# Isolated_Op_Amp.net
KiCad netlist of a schematic drawn in Altium Designer
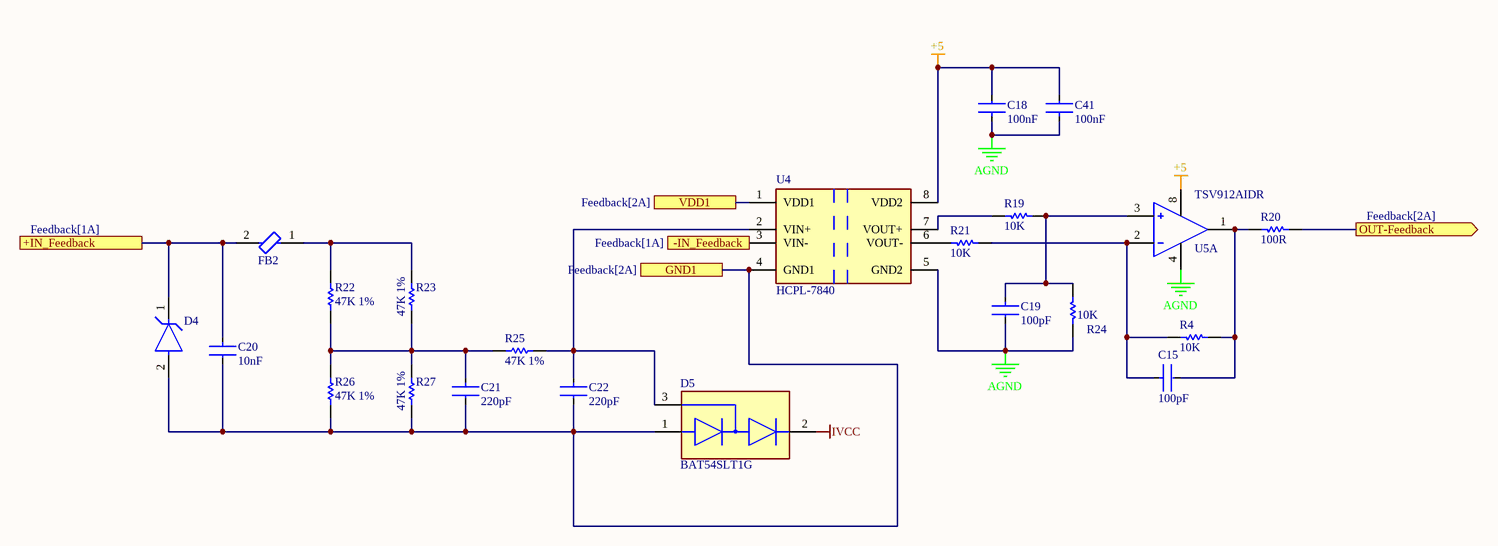
[diagram p0: Isolated Op Amp.SchDoc]

(export (version "E")
  (design (tool "Eeschema 10.0.6"))
  (components
    (comp (ref "C15")
      (value "100pF")
      (footprint "Hosein_PCB_Lib_SMD:CAP-0805")
      (description "Chip Multilayer Ceramic Capacitors for General Purpose, 0603")
      (fields (field (name "VOLTAGE") "6.3V") (field (name "TOLERANCE") "20%"))
      (libsource (lib "Hosein_PCB_Lib") (part "CAP-Ceramic"))
    )
    (comp (ref "C18")
      (value "100nF")
      (footprint "Hosein_PCB_Lib_SMD:CAP-0805")
      (description "Chip Multilayer Ceramic Capacitors for General Purpose, 0603")
      (fields (field (name "VOLTAGE") "6.3V") (field (name "TOLERANCE") "20%"))
      (libsource (lib "Hosein_PCB_Lib") (part "CAP-Ceramic"))
    )
    (comp (ref "C19")
      (value "100pF")
      (footprint "Hosein_PCB_Lib_SMD:CAP-0805")
      (description "Chip Multilayer Ceramic Capacitors for General Purpose, 0603")
      (fields (field (name "VOLTAGE") "6.3V") (field (name "TOLERANCE") "20%"))
      (libsource (lib "Hosein_PCB_Lib") (part "CAP-Ceramic"))
    )
    (comp (ref "C20")
      (value "10nF")
      (footprint "Hosein_PCB_Lib_SMD:CAP-0805")
      (description "Chip Multilayer Ceramic Capacitors for General Purpose, 0603")
      (fields (field (name "VOLTAGE") "6.3V") (field (name "TOLERANCE") "20%"))
      (libsource (lib "Hosein_PCB_Lib") (part "CAP-Ceramic"))
    )
    (comp (ref "C21")
      (value "220pF")
      (footprint "Hosein_PCB_Lib_SMD:CAP-0805")
      (description "Chip Multilayer Ceramic Capacitors for General Purpose, 0603")
      (fields (field (name "VOLTAGE") "6.3V") (field (name "TOLERANCE") "20%"))
      (libsource (lib "Hosein_PCB_Lib") (part "CAP-Ceramic"))
    )
    (comp (ref "C22")
      (value "220pF")
      (footprint "Hosein_PCB_Lib_SMD:CAP-0805")
      (description "Chip Multilayer Ceramic Capacitors for General Purpose, 0603")
      (fields (field (name "VOLTAGE") "6.3V") (field (name "TOLERANCE") "20%"))
      (libsource (lib "Hosein_PCB_Lib") (part "CAP-Ceramic"))
    )
    (comp (ref "C41")
      (value "100nF")
      (footprint "Hosein_PCB_Lib_SMD:CAP-0805")
      (description "Chip Multilayer Ceramic Capacitors for General Purpose, 0603")
      (fields (field (name "VOLTAGE") "6.3V") (field (name "TOLERANCE") "20%"))
      (libsource (lib "Hosein_PCB_Lib") (part "CAP-Ceramic"))
    )
    (comp (ref "D4")
      (value "SMBJ12")
      (footprint "FP-SMB-MFG")
      (description "TVS DIODE SMB")
      (fields
        (field (name "MANUFACTURER") "STMicroelectronics")
        (field (name "MANUFACTURER PART NUMBER") "SMBJ5.0A-TR")
      )
      (libsource (lib "Altium Content Vault") (part "7ddec9f632b8482e96f7745d0fbdf39"))
    )
    (comp (ref "D5")
      (value "BAT54SLT1G")
      (footprint "FP-318-08-IPC_B")
      (description "DIODE ARRAY SCHOTTKY 30V SOT23-3")
      (libsource (lib "Altium Content Vault") (part "cd4ed45a2b9de5095685adb7d6d9b5b"))
    )
    (comp (ref "FB2")
      (value "Ferrite Bead")
      (footprint "FP-BLM31-0_2-t1_1-MFG")
      (description "1206")
      (fields (field (name "TOLERANCE") "25%"))
      (libsource (lib "Altium Content Vault") (part "5f30dd21d616792df468990f7003faa"))
    )
    (comp (ref "R4")
      (value "10K")
      (footprint "Hosein_PCB_Lib_SMD:RES-0805")
      (description "Chip Resistor")
      (fields (field (name "MANUFACTURER") "Vishay Semiconductor"))
      (libsource (lib "Hosein_PCB_Lib") (part "RES_SMD"))
    )
    (comp (ref "R19")
      (value "10K")
      (footprint "Hosein_PCB_Lib_SMD:RES-0805")
      (description "Chip Resistor")
      (fields (field (name "MANUFACTURER") "Vishay Semiconductor"))
      (libsource (lib "Hosein_PCB_Lib") (part "RES_SMD"))
    )
    (comp (ref "R20")
      (value "100R")
      (footprint "Hosein_PCB_Lib_SMD:RES-0805")
      (description "Chip Resistor")
      (fields (field (name "MANUFACTURER") "Vishay Semiconductor"))
      (libsource (lib "Hosein_PCB_Lib") (part "RES_SMD"))
    )
    (comp (ref "R21")
      (value "10K")
      (footprint "Hosein_PCB_Lib_SMD:RES-0805")
      (description "Chip Resistor")
      (fields (field (name "MANUFACTURER") "Vishay Semiconductor"))
      (libsource (lib "Hosein_PCB_Lib") (part "RES_SMD"))
    )
    (comp (ref "R22")
      (value "47K 1%")
      (footprint "Hosein_PCB_Lib_SMD:RES-0805")
      (description "Resistor")
      (fields
        (field (name "TOLERANCE") "5%")
        (field (name "POWER") "1/8 W")
        (field (name "DESIGNER") "Eng. Saeid Jorablo")
        (field (name "PUBLISHER") "SJ Unlimited")
      )
      (libsource (lib "Passive Components") (part "RES"))
    )
    (comp (ref "R23")
      (value "47K 1%")
      (footprint "Hosein_PCB_Lib_SMD:RES-0805")
      (description "Resistor")
      (fields
        (field (name "TOLERANCE") "5%")
        (field (name "POWER") "1/8 W")
        (field (name "DESIGNER") "Eng. Saeid Jorablo")
        (field (name "PUBLISHER") "SJ Unlimited")
      )
      (libsource (lib "Passive Components") (part "RES"))
    )
    (comp (ref "R24")
      (value "10K")
      (footprint "Hosein_PCB_Lib_SMD:RES-0805")
      (description "Chip Resistor")
      (fields (field (name "MANUFACTURER") "Vishay Semiconductor"))
      (libsource (lib "Hosein_PCB_Lib") (part "RES_SMD"))
    )
    (comp (ref "R25")
      (value "47K 1%")
      (footprint "Hosein_PCB_Lib_SMD:RES-0805")
      (description "Resistor")
      (fields
        (field (name "TOLERANCE") "5%")
        (field (name "POWER") "1/8 W")
        (field (name "DESIGNER") "Eng. Saeid Jorablo")
        (field (name "PUBLISHER") "SJ Unlimited")
      )
      (libsource (lib "Passive Components") (part "RES"))
    )
    (comp (ref "R26")
      (value "47K 1%")
      (footprint "Hosein_PCB_Lib_SMD:RES-0805")
      (description "Resistor")
      (fields
        (field (name "TOLERANCE") "5%")
        (field (name "POWER") "1/8 W")
        (field (name "DESIGNER") "Eng. Saeid Jorablo")
        (field (name "PUBLISHER") "SJ Unlimited")
      )
      (libsource (lib "Passive Components") (part "RES"))
    )
    (comp (ref "R27")
      (value "47K 1%")
      (footprint "Hosein_PCB_Lib_SMD:RES-0805")
      (description "Resistor")
      (fields
        (field (name "TOLERANCE") "5%")
        (field (name "POWER") "1/8 W")
        (field (name "DESIGNER") "Eng. Saeid Jorablo")
        (field (name "PUBLISHER") "SJ Unlimited")
      )
      (libsource (lib "Passive Components") (part "RES"))
    )
    (comp (ref "U4")
      (value "HCPL-7840")
      (footprint "FP-HCPL-7800-000E-MFG")
      (description "IC OPAMP ISOLATION 1 CIRC 8DIP")
      (fields (field (name "VOLTAGE") "5V"))
      (libsource (lib "Altium Content Vault") (part "2f7dad3764c767f6029bf863b3cb099"))
    )
    (comp (ref "U5")
      (value "TSV912AIDR")
      (footprint "FP-D0008A-MFG")
      (description "IC OPAMP GP 2 CIRCUIT 8SOIC")
      (libsource (lib "Altium Content Vault") (part "9685343c43c352196e7b040df9e4583"))
    )
  )
  (nets
    (net (code "1") (name "+5") (class "Default")
      (node (ref "C18") (pin "2") (pinfunction "2_2") (pintype "passive"))
      (node (ref "C41") (pin "2") (pinfunction "2_2") (pintype "passive"))
      (node (ref "U4") (pin "8") (pinfunction "VDD2_8") (pintype "power_in"))
      (node (ref "U5") (pin "8") (pinfunction "V+_8") (pintype "power_in"))
    )
    (net (code "2") (name "/+IN_Feedback") (class "Default")
      (node (ref "C20") (pin "1") (pinfunction "1_1") (pintype "passive"))
      (node (ref "D4") (pin "1") (pinfunction "K_1") (pintype "passive"))
      (node (ref "FB2") (pin "2") (pinfunction "2_2") (pintype "passive"))
    )
    (net (code "3") (name "/-IN_Feedback") (class "Default")
      (node (ref "U4") (pin "3") (pinfunction "VIN-_3") (pintype "passive"))
    )
    (net (code "4") (name "/GND1") (class "Default")
      (node (ref "C20") (pin "2") (pinfunction "2_2") (pintype "passive"))
      (node (ref "C21") (pin "2") (pinfunction "2_2") (pintype "passive"))
      (node (ref "C22") (pin "2") (pinfunction "2_2") (pintype "passive"))
      (node (ref "D4") (pin "2") (pinfunction "A_2") (pintype "passive"))
      (node (ref "D5") (pin "1") (pinfunction "A_1") (pintype "passive"))
      (node (ref "R26") (pin "2") (pinfunction "2_2") (pintype "passive"))
      (node (ref "R27") (pin "1") (pinfunction "1_1") (pintype "passive"))
      (node (ref "U4") (pin "4") (pinfunction "GND1_4") (pintype "power_in"))
    )
    (net (code "5") (name "/OUT-Feedback") (class "Default")
      (node (ref "R20") (pin "1") (pinfunction "1_1") (pintype "passive"))
    )
    (net (code "6") (name "/VDD1") (class "Default")
      (node (ref "U4") (pin "1") (pinfunction "VDD1_1") (pintype "power_in"))
    )
    (net (code "7") (name "AGND") (class "Default")
      (node (ref "C18") (pin "1") (pinfunction "1_1") (pintype "passive"))
      (node (ref "C19") (pin "2") (pinfunction "2_2") (pintype "passive"))
      (node (ref "C41") (pin "1") (pinfunction "1_1") (pintype "passive"))
      (node (ref "R24") (pin "1") (pinfunction "1_1") (pintype "passive"))
      (node (ref "U4") (pin "5") (pinfunction "GND2_5") (pintype "power_in"))
      (node (ref "U5") (pin "4") (pinfunction "V-_4") (pintype "power_in"))
    )
    (net (code "8") (name "IVCC") (class "Default")
      (node (ref "D5") (pin "2") (pinfunction "C_2") (pintype "passive"))
    )
    (net (code "9") (name "Net-(C21-Pad1)") (class "Default")
      (node (ref "C21") (pin "1") (pinfunction "1_1") (pintype "passive"))
      (node (ref "R22") (pin "2") (pinfunction "2_2") (pintype "passive"))
      (node (ref "R23") (pin "1") (pinfunction "1_1") (pintype "passive"))
      (node (ref "R25") (pin "2") (pinfunction "2_2") (pintype "passive"))
      (node (ref "R26") (pin "1") (pinfunction "1_1") (pintype "passive"))
      (node (ref "R27") (pin "2") (pinfunction "2_2") (pintype "passive"))
    )
    (net (code "10") (name "Net-(D5-CATHODE{slash}ANODE)") (class "Default")
      (node (ref "C22") (pin "1") (pinfunction "1_1") (pintype "passive"))
      (node (ref "D5") (pin "3") (pinfunction "CATHODE/ANODE_3") (pintype "passive"))
      (node (ref "R25") (pin "1") (pinfunction "1_1") (pintype "passive"))
      (node (ref "U4") (pin "2") (pinfunction "VIN+_2") (pintype "tri_state"))
    )
    (net (code "11") (name "Net-(FB2-Pad1)") (class "Default")
      (node (ref "FB2") (pin "1") (pinfunction "1_1") (pintype "passive"))
      (node (ref "R22") (pin "1") (pinfunction "1_1") (pintype "passive"))
      (node (ref "R23") (pin "2") (pinfunction "2_2") (pintype "passive"))
    )
    (net (code "12") (name "Net-(U4-VOUT+)") (class "Default")
      (node (ref "R19") (pin "2") (pinfunction "2_2") (pintype "passive"))
      (node (ref "U4") (pin "7") (pinfunction "VOUT+_7") (pintype "passive"))
    )
    (net (code "13") (name "Net-(U4-VOUT-)") (class "Default")
      (node (ref "R21") (pin "2") (pinfunction "2_2") (pintype "passive"))
      (node (ref "U4") (pin "6") (pinfunction "VOUT-_6") (pintype "passive"))
    )
    (net (code "14") (name "Net-(U5A-+IN_A)") (class "Default")
      (node (ref "C19") (pin "1") (pinfunction "1_1") (pintype "passive"))
      (node (ref "R19") (pin "1") (pinfunction "1_1") (pintype "passive"))
      (node (ref "R24") (pin "2") (pinfunction "2_2") (pintype "passive"))
      (node (ref "U5") (pin "3") (pinfunction "+IN_A_3") (pintype "tri_state"))
    )
    (net (code "15") (name "Net-(U5A--IN_A)") (class "Default")
      (node (ref "C15") (pin "1") (pinfunction "1_1") (pintype "passive"))
      (node (ref "R21") (pin "1") (pinfunction "1_1") (pintype "passive"))
      (node (ref "R4") (pin "1") (pinfunction "1_1") (pintype "passive"))
      (node (ref "U5") (pin "2") (pinfunction "-IN_A_2") (pintype "tri_state"))
    )
    (net (code "16") (name "Net-(U5A-OUT_A)") (class "Default")
      (node (ref "C15") (pin "2") (pinfunction "2_2") (pintype "passive"))
      (node (ref "R20") (pin "2") (pinfunction "2_2") (pintype "passive"))
      (node (ref "R4") (pin "2") (pinfunction "2_2") (pintype "passive"))
      (node (ref "U5") (pin "1") (pinfunction "OUT_A_1") (pintype "passive"))
    )
  )
)
